# OGX360I-4CH_-_Programming_Utility.net
KiCad netlist of a schematic drawn in EAGLE
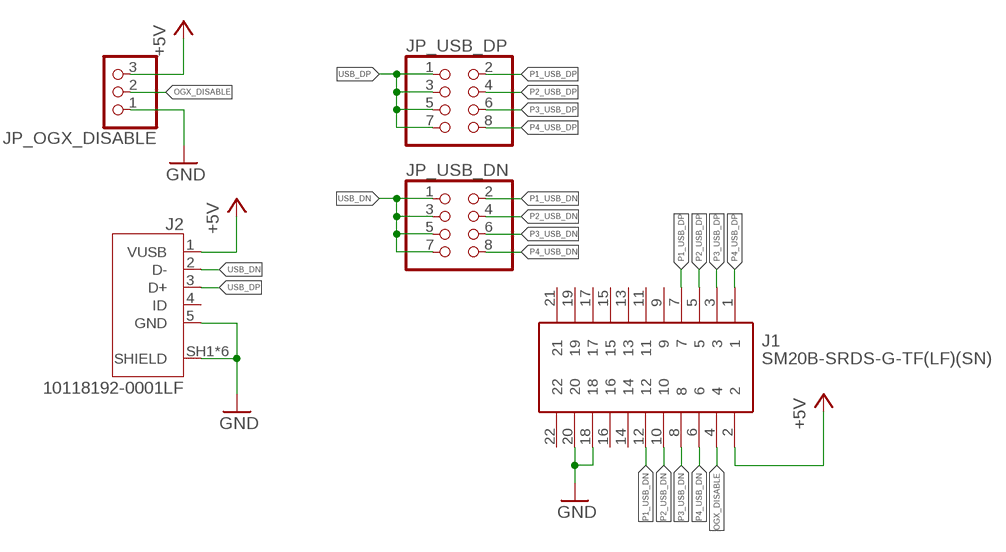
[diagram p0: schematic, sheet 1]

(export (version "E")
  (design (tool "Eeschema 10.0.6"))
  (components
    (comp (ref "J1")
      (value "SM20B-SRDS-G-TF(LF)(SN)")
      (footprint "eagle-import:SM20BSRDSGTFLFSN")
      (libsource (lib "eagle-import") (part "SM20B-SRDS-G-TF(LF)(SN)"))
    )
    (comp (ref "J2")
      (value "10118192-0001LF")
      (footprint "eagle-import:AMPHENOL_10118192-0001LF")
      (fields (field (name "MF") "Amphenol ICC (FCI)"))
      (libsource (lib "eagle-import") (part "10118192-0001LF"))
    )
    (comp (ref "JP_OGX_DISABLE")
      (value "PINHD-1X3")
      (footprint "eagle-import:1X03")
      (libsource (lib "eagle-import") (part "PINHD-1X3"))
    )
    (comp (ref "JP_USB_DN")
      (value "PINHD-2X4")
      (footprint "eagle-import:2X04")
      (libsource (lib "eagle-import") (part "PINHD-2X4"))
    )
    (comp (ref "JP_USB_DP")
      (value "PINHD-2X4")
      (footprint "eagle-import:2X04")
      (libsource (lib "eagle-import") (part "PINHD-2X4"))
    )
  )
  (nets
    (net (code "1") (name "+5V") (class "Default")
      (node (ref "J1") (pin "2") (pinfunction "2_2") (pintype "bidirectional"))
      (node (ref "J2") (pin "1") (pinfunction "VUSB_1") (pintype "passive"))
      (node (ref "JP_OGX_DISABLE") (pin "3") (pinfunction "3_3") (pintype "passive"))
    )
    (net (code "2") (name "GND") (class "Default")
      (node (ref "J1") (pin "18") (pinfunction "18_18") (pintype "bidirectional"))
      (node (ref "J1") (pin "20") (pinfunction "20_20") (pintype "bidirectional"))
      (node (ref "J2") (pin "5") (pinfunction "GND_5") (pintype "passive"))
      (node (ref "J2") (pin "SH1") (pinfunction "SHIELD_SH1") (pintype "passive"))
      (node (ref "J2") (pin "SH2") (pinfunction "SHIELD_SH2") (pintype "passive"))
      (node (ref "J2") (pin "SH3") (pinfunction "SHIELD_SH3") (pintype "passive"))
      (node (ref "J2") (pin "SH4") (pinfunction "SHIELD_SH4") (pintype "passive"))
      (node (ref "J2") (pin "SH5") (pinfunction "SHIELD_SH5") (pintype "passive"))
      (node (ref "J2") (pin "SH6") (pinfunction "SHIELD_SH6") (pintype "passive"))
      (node (ref "JP_OGX_DISABLE") (pin "1") (pinfunction "1_1") (pintype "passive"))
    )
    (net (code "3") (name "OGX_DISABLE") (class "Default")
      (node (ref "J1") (pin "4") (pinfunction "4_4") (pintype "bidirectional"))
      (node (ref "JP_OGX_DISABLE") (pin "2") (pinfunction "2_2") (pintype "passive"))
    )
    (net (code "4") (name "P1_USB_DN") (class "Default")
      (node (ref "J1") (pin "12") (pinfunction "12_12") (pintype "bidirectional"))
      (node (ref "JP_USB_DN") (pin "2") (pinfunction "2_2") (pintype "passive"))
    )
    (net (code "5") (name "P1_USB_DP") (class "Default")
      (node (ref "J1") (pin "7") (pinfunction "7_7") (pintype "bidirectional"))
      (node (ref "JP_USB_DP") (pin "2") (pinfunction "2_2") (pintype "passive"))
    )
    (net (code "6") (name "P2_USB_DN") (class "Default")
      (node (ref "J1") (pin "10") (pinfunction "10_10") (pintype "bidirectional"))
      (node (ref "JP_USB_DN") (pin "4") (pinfunction "4_4") (pintype "passive"))
    )
    (net (code "7") (name "P2_USB_DP") (class "Default")
      (node (ref "J1") (pin "5") (pinfunction "5_5") (pintype "bidirectional"))
      (node (ref "JP_USB_DP") (pin "4") (pinfunction "4_4") (pintype "passive"))
    )
    (net (code "8") (name "P3_USB_DN") (class "Default")
      (node (ref "J1") (pin "8") (pinfunction "8_8") (pintype "bidirectional"))
      (node (ref "JP_USB_DN") (pin "6") (pinfunction "6_6") (pintype "passive"))
    )
    (net (code "9") (name "P3_USB_DP") (class "Default")
      (node (ref "J1") (pin "3") (pinfunction "3_3") (pintype "bidirectional"))
      (node (ref "JP_USB_DP") (pin "6") (pinfunction "6_6") (pintype "passive"))
    )
    (net (code "10") (name "P4_USB_DN") (class "Default")
      (node (ref "J1") (pin "6") (pinfunction "6_6") (pintype "bidirectional"))
      (node (ref "JP_USB_DN") (pin "8") (pinfunction "8_8") (pintype "passive"))
    )
    (net (code "11") (name "P4_USB_DP") (class "Default")
      (node (ref "J1") (pin "1") (pinfunction "1_1") (pintype "bidirectional"))
      (node (ref "JP_USB_DP") (pin "8") (pinfunction "8_8") (pintype "passive"))
    )
    (net (code "12") (name "USB_DN") (class "Default")
      (node (ref "J2") (pin "2") (pinfunction "D-_2") (pintype "passive"))
      (node (ref "JP_USB_DN") (pin "1") (pinfunction "1_1") (pintype "passive"))
      (node (ref "JP_USB_DN") (pin "3") (pinfunction "3_3") (pintype "passive"))
      (node (ref "JP_USB_DN") (pin "5") (pinfunction "5_5") (pintype "passive"))
      (node (ref "JP_USB_DN") (pin "7") (pinfunction "7_7") (pintype "passive"))
    )
    (net (code "13") (name "USB_DP") (class "Default")
      (node (ref "J2") (pin "3") (pinfunction "D+_3") (pintype "passive"))
      (node (ref "JP_USB_DP") (pin "1") (pinfunction "1_1") (pintype "passive"))
      (node (ref "JP_USB_DP") (pin "3") (pinfunction "3_3") (pintype "passive"))
      (node (ref "JP_USB_DP") (pin "5") (pinfunction "5_5") (pintype "passive"))
      (node (ref "JP_USB_DP") (pin "7") (pinfunction "7_7") (pintype "passive"))
    )
    (net (code "14") (name "unconnected-(J1-Pad9)") (class "Default")
      (node (ref "J1") (pin "9") (pinfunction "9_9") (pintype "bidirectional"))
    )
    (net (code "15") (name "unconnected-(J1-Pad11)") (class "Default")
      (node (ref "J1") (pin "11") (pinfunction "11_11") (pintype "bidirectional"))
    )
    (net (code "16") (name "unconnected-(J1-Pad13)") (class "Default")
      (node (ref "J1") (pin "13") (pinfunction "13_13") (pintype "bidirectional"))
    )
    (net (code "17") (name "unconnected-(J1-Pad14)") (class "Default")
      (node (ref "J1") (pin "14") (pinfunction "14_14") (pintype "bidirectional"))
    )
    (net (code "18") (name "unconnected-(J1-Pad15)") (class "Default")
      (node (ref "J1") (pin "15") (pinfunction "15_15") (pintype "bidirectional"))
    )
    (net (code "19") (name "unconnected-(J1-Pad16)") (class "Default")
      (node (ref "J1") (pin "16") (pinfunction "16_16") (pintype "bidirectional"))
    )
    (net (code "20") (name "unconnected-(J1-Pad17)") (class "Default")
      (node (ref "J1") (pin "17") (pinfunction "17_17") (pintype "bidirectional"))
    )
    (net (code "21") (name "unconnected-(J1-Pad19)") (class "Default")
      (node (ref "J1") (pin "19") (pinfunction "19_19") (pintype "bidirectional"))
    )
    (net (code "22") (name "unconnected-(J1-Pad21)") (class "Default")
      (node (ref "J1") (pin "21") (pinfunction "21_21") (pintype "bidirectional"))
    )
    (net (code "23") (name "unconnected-(J1-Pad22)") (class "Default")
      (node (ref "J1") (pin "22") (pinfunction "22_22") (pintype "bidirectional"))
    )
    (net (code "24") (name "unconnected-(J2-ID-Pad4)") (class "Default")
      (node (ref "J2") (pin "4") (pinfunction "ID_4") (pintype "passive"))
    )
  )
)
